# schematic.net
KiCad netlist of a schematic drawn in Altium Designer
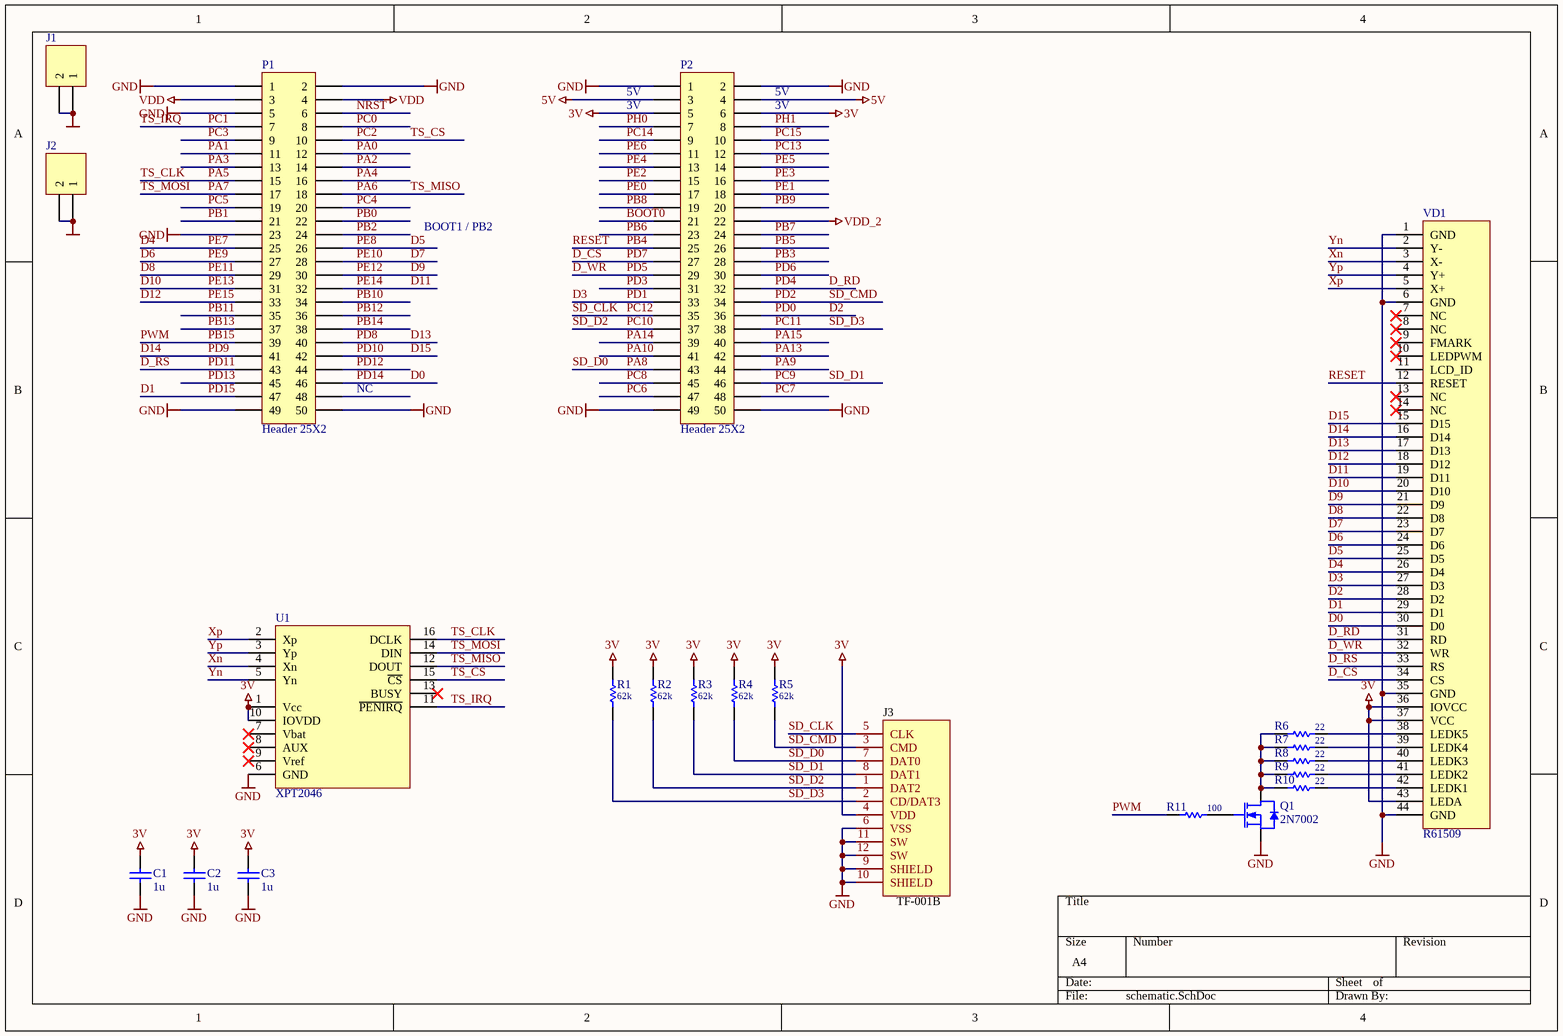
[diagram p0: schematic.SchDoc]

(export (version "E")
  (design (tool "Eeschema 10.0.6"))
  (components
    (comp (ref "C1") (value "1u") (footprint "C0603") (libsource (lib "Miscellaneous Devices") (part "Cap")))
    (comp (ref "C2") (value "1u") (footprint "C0603") (libsource (lib "Miscellaneous Devices") (part "Cap")))
    (comp (ref "C3") (value "1u") (footprint "C0603") (libsource (lib "Miscellaneous Devices") (part "Cap")))
    (comp (ref "J1") (value "Header 2") (footprint "HDR_1X2") (libsource (lib "Schlib1") (part "Header 2")))
    (comp (ref "J2") (value "Header 2") (footprint "HDR_1X2") (libsource (lib "Schlib1") (part "Header 2")))
    (comp (ref "J3")
      (value "TF-001B")
      (footprint "TF-SMD_TF-001B")
      (fields (field (name "MANUFACTURER") "SOFNG(硕方)"))
      (libsource (lib "Schlib1") (part "TF-001B"))
    )
    (comp (ref "P1")
      (value "Header 25X2")
      (footprint "HDR_2X25")
      (description "Header, 25-Pin, Dual row")
      (fields (field (name "PUBLISHER") "Altium Limited"))
      (libsource (lib "Miscellaneous Connectors") (part "Header 25X2"))
    )
    (comp (ref "P2")
      (value "Header 25X2")
      (footprint "HDR_2X25")
      (description "Header, 25-Pin, Dual row")
      (fields (field (name "PUBLISHER") "Altium Limited"))
      (libsource (lib "Miscellaneous Connectors") (part "Header 25X2"))
    )
    (comp (ref "Q1")
      (value "2N7002")
      (footprint "SOT-23")
      (libsource (lib "Miscellaneous Devices") (part "2N7002"))
    )
    (comp (ref "R1") (value "62k") (footprint "R0805") (libsource (lib "RR_Passive") (part "RES")))
    (comp (ref "R2") (value "62k") (footprint "R0805") (libsource (lib "RR_Passive") (part "RES")))
    (comp (ref "R3") (value "62k") (footprint "R0805") (libsource (lib "RR_Passive") (part "RES")))
    (comp (ref "R4") (value "62k") (footprint "R0805") (libsource (lib "RR_Passive") (part "RES")))
    (comp (ref "R5") (value "62k") (footprint "R0805") (libsource (lib "RR_Passive") (part "RES")))
    (comp (ref "R6") (value "22") (footprint "R0603") (libsource (lib "RR_Passive") (part "RES")))
    (comp (ref "R7") (value "22") (footprint "R0603") (libsource (lib "RR_Passive") (part "RES")))
    (comp (ref "R8") (value "22") (footprint "R0603") (libsource (lib "RR_Passive") (part "RES")))
    (comp (ref "R9") (value "22") (footprint "R0603") (libsource (lib "RR_Passive") (part "RES")))
    (comp (ref "R10") (value "22") (footprint "R0603") (libsource (lib "RR_Passive") (part "RES")))
    (comp (ref "R11") (value "100") (footprint "R0603") (libsource (lib "RR_Passive") (part "RES")))
    (comp (ref "U1") (value "XPT2046") (footprint "TSSOP-16") (libsource (lib "Schlib1") (part "U?")))
    (comp (ref "VD1")
      (value "R61509")
      (footprint "TFT_3.2inch")
      (libsource (lib "Schlib1") (part "R61509_TFT"))
    )
  )
  (nets
    (net (code "1") (name "/BOOT0") (class "Default")
      (node (ref "P2") (pin "21") (pinfunction "21_21") (pintype "passive"))
    )
    (net (code "2") (name "/D0") (class "Default")
      (node (ref "P1") (pin "46") (pinfunction "46_46") (pintype "passive"))
      (node (ref "VD1") (pin "30") (pinfunction "D0_30") (pintype "passive"))
    )
    (net (code "3") (name "/D1") (class "Default")
      (node (ref "P1") (pin "47") (pinfunction "47_47") (pintype "passive"))
      (node (ref "VD1") (pin "29") (pinfunction "D1_29") (pintype "passive"))
    )
    (net (code "4") (name "/D2") (class "Default")
      (node (ref "P2") (pin "36") (pinfunction "36_36") (pintype "passive"))
      (node (ref "VD1") (pin "28") (pinfunction "D2_28") (pintype "passive"))
    )
    (net (code "5") (name "/D3") (class "Default")
      (node (ref "P2") (pin "33") (pinfunction "33_33") (pintype "passive"))
      (node (ref "VD1") (pin "27") (pinfunction "D3_27") (pintype "passive"))
    )
    (net (code "6") (name "/D4") (class "Default")
      (node (ref "P1") (pin "25") (pinfunction "25_25") (pintype "passive"))
      (node (ref "VD1") (pin "26") (pinfunction "D4_26") (pintype "passive"))
    )
    (net (code "7") (name "/D5") (class "Default")
      (node (ref "P1") (pin "26") (pinfunction "26_26") (pintype "passive"))
      (node (ref "VD1") (pin "25") (pinfunction "D5_25") (pintype "passive"))
    )
    (net (code "8") (name "/D6") (class "Default")
      (node (ref "P1") (pin "27") (pinfunction "27_27") (pintype "passive"))
      (node (ref "VD1") (pin "24") (pinfunction "D6_24") (pintype "passive"))
    )
    (net (code "9") (name "/D7") (class "Default")
      (node (ref "P1") (pin "28") (pinfunction "28_28") (pintype "passive"))
      (node (ref "VD1") (pin "23") (pinfunction "D7_23") (pintype "passive"))
    )
    (net (code "10") (name "/D8") (class "Default")
      (node (ref "P1") (pin "29") (pinfunction "29_29") (pintype "passive"))
      (node (ref "VD1") (pin "22") (pinfunction "D8_22") (pintype "passive"))
    )
    (net (code "11") (name "/D9") (class "Default")
      (node (ref "P1") (pin "30") (pinfunction "30_30") (pintype "passive"))
      (node (ref "VD1") (pin "21") (pinfunction "D9_21") (pintype "passive"))
    )
    (net (code "12") (name "/D10") (class "Default")
      (node (ref "P1") (pin "31") (pinfunction "31_31") (pintype "passive"))
      (node (ref "VD1") (pin "20") (pinfunction "D10_20") (pintype "passive"))
    )
    (net (code "13") (name "/D11") (class "Default")
      (node (ref "P1") (pin "32") (pinfunction "32_32") (pintype "passive"))
      (node (ref "VD1") (pin "19") (pinfunction "D11_19") (pintype "passive"))
    )
    (net (code "14") (name "/D12") (class "Default")
      (node (ref "P1") (pin "33") (pinfunction "33_33") (pintype "passive"))
      (node (ref "VD1") (pin "18") (pinfunction "D12_18") (pintype "passive"))
    )
    (net (code "15") (name "/D13") (class "Default")
      (node (ref "P1") (pin "40") (pinfunction "40_40") (pintype "passive"))
      (node (ref "VD1") (pin "17") (pinfunction "D13_17") (pintype "passive"))
    )
    (net (code "16") (name "/D14") (class "Default")
      (node (ref "P1") (pin "41") (pinfunction "41_41") (pintype "passive"))
      (node (ref "VD1") (pin "16") (pinfunction "D14_16") (pintype "passive"))
    )
    (net (code "17") (name "/D15") (class "Default")
      (node (ref "P1") (pin "42") (pinfunction "42_42") (pintype "passive"))
      (node (ref "VD1") (pin "15") (pinfunction "D15_15") (pintype "passive"))
    )
    (net (code "18") (name "/D_CS") (class "Default")
      (node (ref "P2") (pin "27") (pinfunction "27_27") (pintype "passive"))
      (node (ref "VD1") (pin "34") (pinfunction "CS_34") (pintype "passive"))
    )
    (net (code "19") (name "/D_RD") (class "Default")
      (node (ref "P2") (pin "32") (pinfunction "32_32") (pintype "passive"))
      (node (ref "VD1") (pin "31") (pinfunction "RD_31") (pintype "passive"))
    )
    (net (code "20") (name "/D_RS") (class "Default")
      (node (ref "P1") (pin "43") (pinfunction "43_43") (pintype "passive"))
      (node (ref "VD1") (pin "33") (pinfunction "RS_33") (pintype "passive"))
    )
    (net (code "21") (name "/D_WR") (class "Default")
      (node (ref "P2") (pin "29") (pinfunction "29_29") (pintype "passive"))
      (node (ref "VD1") (pin "32") (pinfunction "WR_32") (pintype "passive"))
    )
    (net (code "22") (name "/NRST") (class "Default")
      (node (ref "P1") (pin "6") (pinfunction "6_6") (pintype "passive"))
    )
    (net (code "23") (name "/PA0") (class "Default")
      (node (ref "P1") (pin "12") (pinfunction "12_12") (pintype "passive"))
    )
    (net (code "24") (name "/PA1") (class "Default")
      (node (ref "P1") (pin "11") (pinfunction "11_11") (pintype "passive"))
    )
    (net (code "25") (name "/PA2") (class "Default")
      (node (ref "P1") (pin "14") (pinfunction "14_14") (pintype "passive"))
    )
    (net (code "26") (name "/PA3") (class "Default")
      (node (ref "P1") (pin "13") (pinfunction "13_13") (pintype "passive"))
    )
    (net (code "27") (name "/PA4") (class "Default")
      (node (ref "P1") (pin "16") (pinfunction "16_16") (pintype "passive"))
    )
    (net (code "28") (name "/PA5") (class "Default")
      (node (ref "P1") (pin "15") (pinfunction "15_15") (pintype "passive"))
      (node (ref "U1") (pin "16") (pinfunction "DCLK_16") (pintype "passive"))
    )
    (net (code "29") (name "/PA6") (class "Default")
      (node (ref "P1") (pin "18") (pinfunction "18_18") (pintype "passive"))
      (node (ref "U1") (pin "12") (pinfunction "DOUT_12") (pintype "passive"))
    )
    (net (code "30") (name "/PA7") (class "Default")
      (node (ref "P1") (pin "17") (pinfunction "17_17") (pintype "passive"))
      (node (ref "U1") (pin "14") (pinfunction "DIN_14") (pintype "passive"))
    )
    (net (code "31") (name "/PA8") (class "Default")
      (node (ref "J3") (pin "7") (pinfunction "DAT0_7") (pintype "passive"))
      (node (ref "P2") (pin "43") (pinfunction "43_43") (pintype "passive"))
      (node (ref "R4") (pin "2") (pinfunction "2_2") (pintype "passive"))
    )
    (net (code "32") (name "/PA9") (class "Default")
      (node (ref "P2") (pin "44") (pinfunction "44_44") (pintype "passive"))
    )
    (net (code "33") (name "/PA10") (class "Default")
      (node (ref "P2") (pin "41") (pinfunction "41_41") (pintype "passive"))
    )
    (net (code "34") (name "/PA13") (class "Default")
      (node (ref "P2") (pin "42") (pinfunction "42_42") (pintype "passive"))
    )
    (net (code "35") (name "/PA14") (class "Default")
      (node (ref "P2") (pin "39") (pinfunction "39_39") (pintype "passive"))
    )
    (net (code "36") (name "/PA15") (class "Default")
      (node (ref "P2") (pin "40") (pinfunction "40_40") (pintype "passive"))
    )
    (net (code "37") (name "/PB0") (class "Default")
      (node (ref "P1") (pin "22") (pinfunction "22_22") (pintype "passive"))
    )
    (net (code "38") (name "/PB1") (class "Default")
      (node (ref "P1") (pin "21") (pinfunction "21_21") (pintype "passive"))
    )
    (net (code "39") (name "/PB2") (class "Default")
      (node (ref "P1") (pin "24") (pinfunction "24_24") (pintype "passive"))
    )
    (net (code "40") (name "/PB3") (class "Default")
      (node (ref "P2") (pin "28") (pinfunction "28_28") (pintype "passive"))
    )
    (net (code "41") (name "/PB4") (class "Default")
      (node (ref "P2") (pin "25") (pinfunction "25_25") (pintype "passive"))
      (node (ref "VD1") (pin "12") (pinfunction "RESET_12") (pintype "passive"))
    )
    (net (code "42") (name "/PB5") (class "Default")
      (node (ref "P2") (pin "26") (pinfunction "26_26") (pintype "passive"))
    )
    (net (code "43") (name "/PB6") (class "Default")
      (node (ref "P2") (pin "23") (pinfunction "23_23") (pintype "passive"))
    )
    (net (code "44") (name "/PB7") (class "Default")
      (node (ref "P2") (pin "24") (pinfunction "24_24") (pintype "passive"))
    )
    (net (code "45") (name "/PB8") (class "Default")
      (node (ref "P2") (pin "19") (pinfunction "19_19") (pintype "passive"))
    )
    (net (code "46") (name "/PB9") (class "Default")
      (node (ref "P2") (pin "20") (pinfunction "20_20") (pintype "passive"))
    )
    (net (code "47") (name "/PB10") (class "Default")
      (node (ref "P1") (pin "34") (pinfunction "34_34") (pintype "passive"))
    )
    (net (code "48") (name "/PB11") (class "Default")
      (node (ref "P1") (pin "35") (pinfunction "35_35") (pintype "passive"))
    )
    (net (code "49") (name "/PB12") (class "Default")
      (node (ref "P1") (pin "36") (pinfunction "36_36") (pintype "passive"))
    )
    (net (code "50") (name "/PB13") (class "Default")
      (node (ref "P1") (pin "37") (pinfunction "37_37") (pintype "passive"))
    )
    (net (code "51") (name "/PB14") (class "Default")
      (node (ref "P1") (pin "38") (pinfunction "38_38") (pintype "passive"))
    )
    (net (code "52") (name "/PB15") (class "Default")
      (node (ref "P1") (pin "39") (pinfunction "39_39") (pintype "passive"))
      (node (ref "R11") (pin "1") (pinfunction "1_1") (pintype "passive"))
    )
    (net (code "53") (name "/PC0") (class "Default")
      (node (ref "P1") (pin "8") (pinfunction "8_8") (pintype "passive"))
    )
    (net (code "54") (name "/PC1") (class "Default")
      (node (ref "P1") (pin "7") (pinfunction "7_7") (pintype "passive"))
      (node (ref "U1") (pin "11") (pinfunction "~{PENIRQ}_11") (pintype "passive"))
    )
    (net (code "55") (name "/PC2") (class "Default")
      (node (ref "P1") (pin "10") (pinfunction "10_10") (pintype "passive"))
      (node (ref "U1") (pin "15") (pinfunction "~{CS}_15") (pintype "passive"))
    )
    (net (code "56") (name "/PC3") (class "Default")
      (node (ref "P1") (pin "9") (pinfunction "9_9") (pintype "passive"))
    )
    (net (code "57") (name "/PC4") (class "Default")
      (node (ref "P1") (pin "20") (pinfunction "20_20") (pintype "passive"))
    )
    (net (code "58") (name "/PC5") (class "Default")
      (node (ref "P1") (pin "19") (pinfunction "19_19") (pintype "passive"))
    )
    (net (code "59") (name "/PC6") (class "Default")
      (node (ref "P2") (pin "47") (pinfunction "47_47") (pintype "passive"))
    )
    (net (code "60") (name "/PC7") (class "Default")
      (node (ref "P2") (pin "48") (pinfunction "48_48") (pintype "passive"))
    )
    (net (code "61") (name "/PC8") (class "Default")
      (node (ref "P2") (pin "45") (pinfunction "45_45") (pintype "passive"))
    )
    (net (code "62") (name "/PC9") (class "Default")
      (node (ref "J3") (pin "8") (pinfunction "DAT1_8") (pintype "passive"))
      (node (ref "P2") (pin "46") (pinfunction "46_46") (pintype "passive"))
      (node (ref "R3") (pin "2") (pinfunction "2_2") (pintype "passive"))
    )
    (net (code "63") (name "/PC10") (class "Default")
      (node (ref "J3") (pin "1") (pinfunction "DAT2_1") (pintype "passive"))
      (node (ref "P2") (pin "37") (pinfunction "37_37") (pintype "passive"))
      (node (ref "R2") (pin "2") (pinfunction "2_2") (pintype "passive"))
    )
    (net (code "64") (name "/PC11") (class "Default")
      (node (ref "J3") (pin "2") (pinfunction "CD/DAT3_2") (pintype "passive"))
      (node (ref "P2") (pin "38") (pinfunction "38_38") (pintype "passive"))
      (node (ref "R1") (pin "2") (pinfunction "2_2") (pintype "passive"))
    )
    (net (code "65") (name "/PC12") (class "Default")
      (node (ref "J3") (pin "5") (pinfunction "CLK_5") (pintype "passive"))
      (node (ref "P2") (pin "35") (pinfunction "35_35") (pintype "passive"))
    )
    (net (code "66") (name "/PC13") (class "Default")
      (node (ref "P2") (pin "12") (pinfunction "12_12") (pintype "passive"))
    )
    (net (code "67") (name "/PC14") (class "Default")
      (node (ref "P2") (pin "9") (pinfunction "9_9") (pintype "passive"))
    )
    (net (code "68") (name "/PC15") (class "Default")
      (node (ref "P2") (pin "10") (pinfunction "10_10") (pintype "passive"))
    )
    (net (code "69") (name "/PD2") (class "Default")
      (node (ref "J3") (pin "3") (pinfunction "CMD_3") (pintype "passive"))
      (node (ref "P2") (pin "34") (pinfunction "34_34") (pintype "passive"))
      (node (ref "R5") (pin "2") (pinfunction "2_2") (pintype "passive"))
    )
    (net (code "70") (name "/PD3") (class "Default")
      (node (ref "P2") (pin "31") (pinfunction "31_31") (pintype "passive"))
    )
    (net (code "71") (name "/PD6") (class "Default")
      (node (ref "P2") (pin "30") (pinfunction "30_30") (pintype "passive"))
    )
    (net (code "72") (name "/PD12") (class "Default")
      (node (ref "P1") (pin "44") (pinfunction "44_44") (pintype "passive"))
    )
    (net (code "73") (name "/PD13") (class "Default")
      (node (ref "P1") (pin "45") (pinfunction "45_45") (pintype "passive"))
    )
    (net (code "74") (name "/PE0") (class "Default")
      (node (ref "P2") (pin "17") (pinfunction "17_17") (pintype "passive"))
    )
    (net (code "75") (name "/PE1") (class "Default")
      (node (ref "P2") (pin "18") (pinfunction "18_18") (pintype "passive"))
    )
    (net (code "76") (name "/PE2") (class "Default")
      (node (ref "P2") (pin "15") (pinfunction "15_15") (pintype "passive"))
    )
    (net (code "77") (name "/PE3") (class "Default")
      (node (ref "P2") (pin "16") (pinfunction "16_16") (pintype "passive"))
    )
    (net (code "78") (name "/PE4") (class "Default")
      (node (ref "P2") (pin "13") (pinfunction "13_13") (pintype "passive"))
    )
    (net (code "79") (name "/PE5") (class "Default")
      (node (ref "P2") (pin "14") (pinfunction "14_14") (pintype "passive"))
    )
    (net (code "80") (name "/PE6") (class "Default")
      (node (ref "P2") (pin "11") (pinfunction "11_11") (pintype "passive"))
    )
    (net (code "81") (name "/PH0") (class "Default")
      (node (ref "P2") (pin "7") (pinfunction "7_7") (pintype "passive"))
    )
    (net (code "82") (name "/PH1") (class "Default")
      (node (ref "P2") (pin "8") (pinfunction "8_8") (pintype "passive"))
    )
    (net (code "83") (name "/Xn") (class "Default")
      (node (ref "U1") (pin "4") (pinfunction "Xn_4") (pintype "passive"))
      (node (ref "VD1") (pin "3") (pinfunction "X-_3") (pintype "passive"))
    )
    (net (code "84") (name "/Xp") (class "Default")
      (node (ref "U1") (pin "2") (pinfunction "Xp_2") (pintype "passive"))
      (node (ref "VD1") (pin "5") (pinfunction "X+_5") (pintype "passive"))
    )
    (net (code "85") (name "/Yn") (class "Default")
      (node (ref "U1") (pin "5") (pinfunction "Yn_5") (pintype "passive"))
      (node (ref "VD1") (pin "2") (pinfunction "Y-_2") (pintype "passive"))
    )
    (net (code "86") (name "/Yp") (class "Default")
      (node (ref "U1") (pin "3") (pinfunction "Yp_3") (pintype "passive"))
      (node (ref "VD1") (pin "4") (pinfunction "Y+_4") (pintype "passive"))
    )
    (net (code "87") (name "3V") (class "Default")
      (node (ref "C1") (pin "2") (pinfunction "2_2") (pintype "passive"))
      (node (ref "C2") (pin "2") (pinfunction "2_2") (pintype "passive"))
      (node (ref "C3") (pin "2") (pinfunction "2_2") (pintype "passive"))
      (node (ref "J3") (pin "4") (pinfunction "VDD_4") (pintype "passive"))
      (node (ref "P2") (pin "5") (pinfunction "5_5") (pintype "passive"))
      (node (ref "P2") (pin "6") (pinfunction "6_6") (pintype "passive"))
      (node (ref "R1") (pin "1") (pinfunction "1_1") (pintype "passive"))
      (node (ref "R2") (pin "1") (pinfunction "1_1") (pintype "passive"))
      (node (ref "R3") (pin "1") (pinfunction "1_1") (pintype "passive"))
      (node (ref "R4") (pin "1") (pinfunction "1_1") (pintype "passive"))
      (node (ref "R5") (pin "1") (pinfunction "1_1") (pintype "passive"))
      (node (ref "U1") (pin "1") (pinfunction "Vcc_1") (pintype "passive"))
      (node (ref "U1") (pin "10") (pinfunction "IOVDD_10") (pintype "passive"))
      (node (ref "VD1") (pin "36") (pinfunction "IOVCC_36") (pintype "passive"))
      (node (ref "VD1") (pin "37") (pinfunction "VCC_37") (pintype "passive"))
      (node (ref "VD1") (pin "43") (pinfunction "LEDA_43") (pintype "passive"))
    )
    (net (code "88") (name "5V") (class "Default")
      (node (ref "P2") (pin "3") (pinfunction "3_3") (pintype "passive"))
      (node (ref "P2") (pin "4") (pinfunction "4_4") (pintype "passive"))
    )
    (net (code "89") (name "GND") (class "Default")
      (node (ref "C1") (pin "1") (pinfunction "1_1") (pintype "passive"))
      (node (ref "C2") (pin "1") (pinfunction "1_1") (pintype "passive"))
      (node (ref "C3") (pin "1") (pinfunction "1_1") (pintype "passive"))
      (node (ref "J1") (pin "1") (pinfunction "1_1") (pintype "passive"))
      (node (ref "J1") (pin "2") (pinfunction "2_2") (pintype "passive"))
      (node (ref "J2") (pin "1") (pinfunction "1_1") (pintype "passive"))
      (node (ref "J2") (pin "2") (pinfunction "2_2") (pintype "passive"))
      (node (ref "J3") (pin "10") (pinfunction "SHIELD_10") (pintype "passive"))
      (node (ref "J3") (pin "11") (pinfunction "SW_11") (pintype "passive"))
      (node (ref "J3") (pin "12") (pinfunction "SW_12") (pintype "passive"))
      (node (ref "J3") (pin "6") (pinfunction "VSS_6") (pintype "passive"))
      (node (ref "J3") (pin "9") (pinfunction "SHIELD_9") (pintype "passive"))
      (node (ref "P1") (pin "1") (pinfunction "1_1") (pintype "passive"))
      (node (ref "P1") (pin "2") (pinfunction "2_2") (pintype "passive"))
      (node (ref "P1") (pin "23") (pinfunction "23_23") (pintype "passive"))
      (node (ref "P1") (pin "49") (pinfunction "49_49") (pintype "passive"))
      (node (ref "P1") (pin "5") (pinfunction "5_5") (pintype "passive"))
      (node (ref "P1") (pin "50") (pinfunction "50_50") (pintype "passive"))
      (node (ref "P2") (pin "1") (pinfunction "1_1") (pintype "passive"))
      (node (ref "P2") (pin "2") (pinfunction "2_2") (pintype "passive"))
      (node (ref "P2") (pin "49") (pinfunction "49_49") (pintype "passive"))
      (node (ref "P2") (pin "50") (pinfunction "50_50") (pintype "passive"))
      (node (ref "Q1") (pin "2") (pinfunction "SOURCE_2") (pintype "passive"))
      (node (ref "U1") (pin "6") (pinfunction "GND_6") (pintype "passive"))
      (node (ref "VD1") (pin "1") (pinfunction "GND_1") (pintype "passive"))
      (node (ref "VD1") (pin "35") (pinfunction "GND_35") (pintype "passive"))
      (node (ref "VD1") (pin "44") (pinfunction "GND_44") (pintype "passive"))
      (node (ref "VD1") (pin "6") (pinfunction "GND_6") (pintype "passive"))
    )
    (net (code "90") (name "Net-(Q1-DRAIN)") (class "Default")
      (node (ref "Q1") (pin "3") (pinfunction "DRAIN_3") (pintype "passive"))
      (node (ref "R10") (pin "1") (pinfunction "1_1") (pintype "passive"))
      (node (ref "R6") (pin "1") (pinfunction "1_1") (pintype "passive"))
      (node (ref "R7") (pin "1") (pinfunction "1_1") (pintype "passive"))
      (node (ref "R8") (pin "1") (pinfunction "1_1") (pintype "passive"))
      (node (ref "R9") (pin "1") (pinfunction "1_1") (pintype "passive"))
    )
    (net (code "91") (name "Net-(Q1-GATE)") (class "Default")
      (node (ref "Q1") (pin "1") (pinfunction "GATE_1") (pintype "passive"))
      (node (ref "R11") (pin "2") (pinfunction "2_2") (pintype "passive"))
    )
    (net (code "92") (name "Net-(VD1-LEDK1)") (class "Default")
      (node (ref "R10") (pin "2") (pinfunction "2_2") (pintype "passive"))
      (node (ref "VD1") (pin "42") (pinfunction "LEDK1_42") (pintype "passive"))
    )
    (net (code "93") (name "Net-(VD1-LEDK2)") (class "Default")
      (node (ref "R9") (pin "2") (pinfunction "2_2") (pintype "passive"))
      (node (ref "VD1") (pin "41") (pinfunction "LEDK2_41") (pintype "passive"))
    )
    (net (code "94") (name "Net-(VD1-LEDK3)") (class "Default")
      (node (ref "R8") (pin "2") (pinfunction "2_2") (pintype "passive"))
      (node (ref "VD1") (pin "40") (pinfunction "LEDK3_40") (pintype "passive"))
    )
    (net (code "95") (name "Net-(VD1-LEDK4)") (class "Default")
      (node (ref "R7") (pin "2") (pinfunction "2_2") (pintype "passive"))
      (node (ref "VD1") (pin "39") (pinfunction "LEDK4_39") (pintype "passive"))
    )
    (net (code "96") (name "Net-(VD1-LEDK5)") (class "Default")
      (node (ref "R6") (pin "2") (pinfunction "2_2") (pintype "passive"))
      (node (ref "VD1") (pin "38") (pinfunction "LEDK5_38") (pintype "passive"))
    )
    (net (code "97") (name "VDD") (class "Default")
      (node (ref "P1") (pin "3") (pinfunction "3_3") (pintype "passive"))
      (node (ref "P1") (pin "4") (pinfunction "4_4") (pintype "passive"))
    )
    (net (code "98") (name "VDD_2") (class "Default")
      (node (ref "P2") (pin "22") (pinfunction "22_22") (pintype "passive"))
    )
    (net (code "99") (name "unconnected-(P1-Pad48)") (class "Default")
      (node (ref "P1") (pin "48") (pinfunction "48_48") (pintype "passive"))
    )
    (net (code "100") (name "unconnected-(U1-AUX-Pad8)") (class "Default")
      (node (ref "U1") (pin "8") (pinfunction "AUX_8") (pintype "passive+no_connect"))
    )
    (net (code "101") (name "unconnected-(U1-BUSY-Pad13)") (class "Default")
      (node (ref "U1") (pin "13") (pinfunction "BUSY_13") (pintype "passive+no_connect"))
    )
    (net (code "102") (name "unconnected-(U1-Vbat-Pad7)") (class "Default")
      (node (ref "U1") (pin "7") (pinfunction "Vbat_7") (pintype "passive+no_connect"))
    )
    (net (code "103") (name "unconnected-(U1-Vref-Pad9)") (class "Default")
      (node (ref "U1") (pin "9") (pinfunction "Vref_9") (pintype "passive+no_connect"))
    )
    (net (code "104") (name "unconnected-(VD1-FMARK-Pad9)") (class "Default")
      (node (ref "VD1") (pin "9") (pinfunction "FMARK_9") (pintype "passive+no_connect"))
    )
    (net (code "105") (name "unconnected-(VD1-LCD_ID-Pad11)") (class "Default")
      (node (ref "VD1") (pin "11") (pinfunction "LCD_ID_11") (pintype "passive"))
    )
    (net (code "106") (name "unconnected-(VD1-LEDPWM-Pad10)") (class "Default")
      (node (ref "VD1") (pin "10") (pinfunction "LEDPWM_10") (pintype "passive+no_connect"))
    )
    (net (code "107") (name "unconnected-(VD1-NC-Pad7)") (class "Default")
      (node (ref "VD1") (pin "7") (pinfunction "NC_7") (pintype "passive+no_connect"))
    )
    (net (code "108") (name "unconnected-(VD1-NC-Pad8)") (class "Default")
      (node (ref "VD1") (pin "8") (pinfunction "NC_8") (pintype "passive+no_connect"))
    )
    (net (code "109") (name "unconnected-(VD1-NC-Pad13)") (class "Default")
      (node (ref "VD1") (pin "13") (pinfunction "NC_13") (pintype "passive+no_connect"))
    )
    (net (code "110") (name "unconnected-(VD1-NC-Pad14)") (class "Default")
      (node (ref "VD1") (pin "14") (pinfunction "NC_14") (pintype "passive+no_connect"))
    )
  )
)
